# twister3-controller.net
KiCad netlist of a schematic drawn in EAGLE
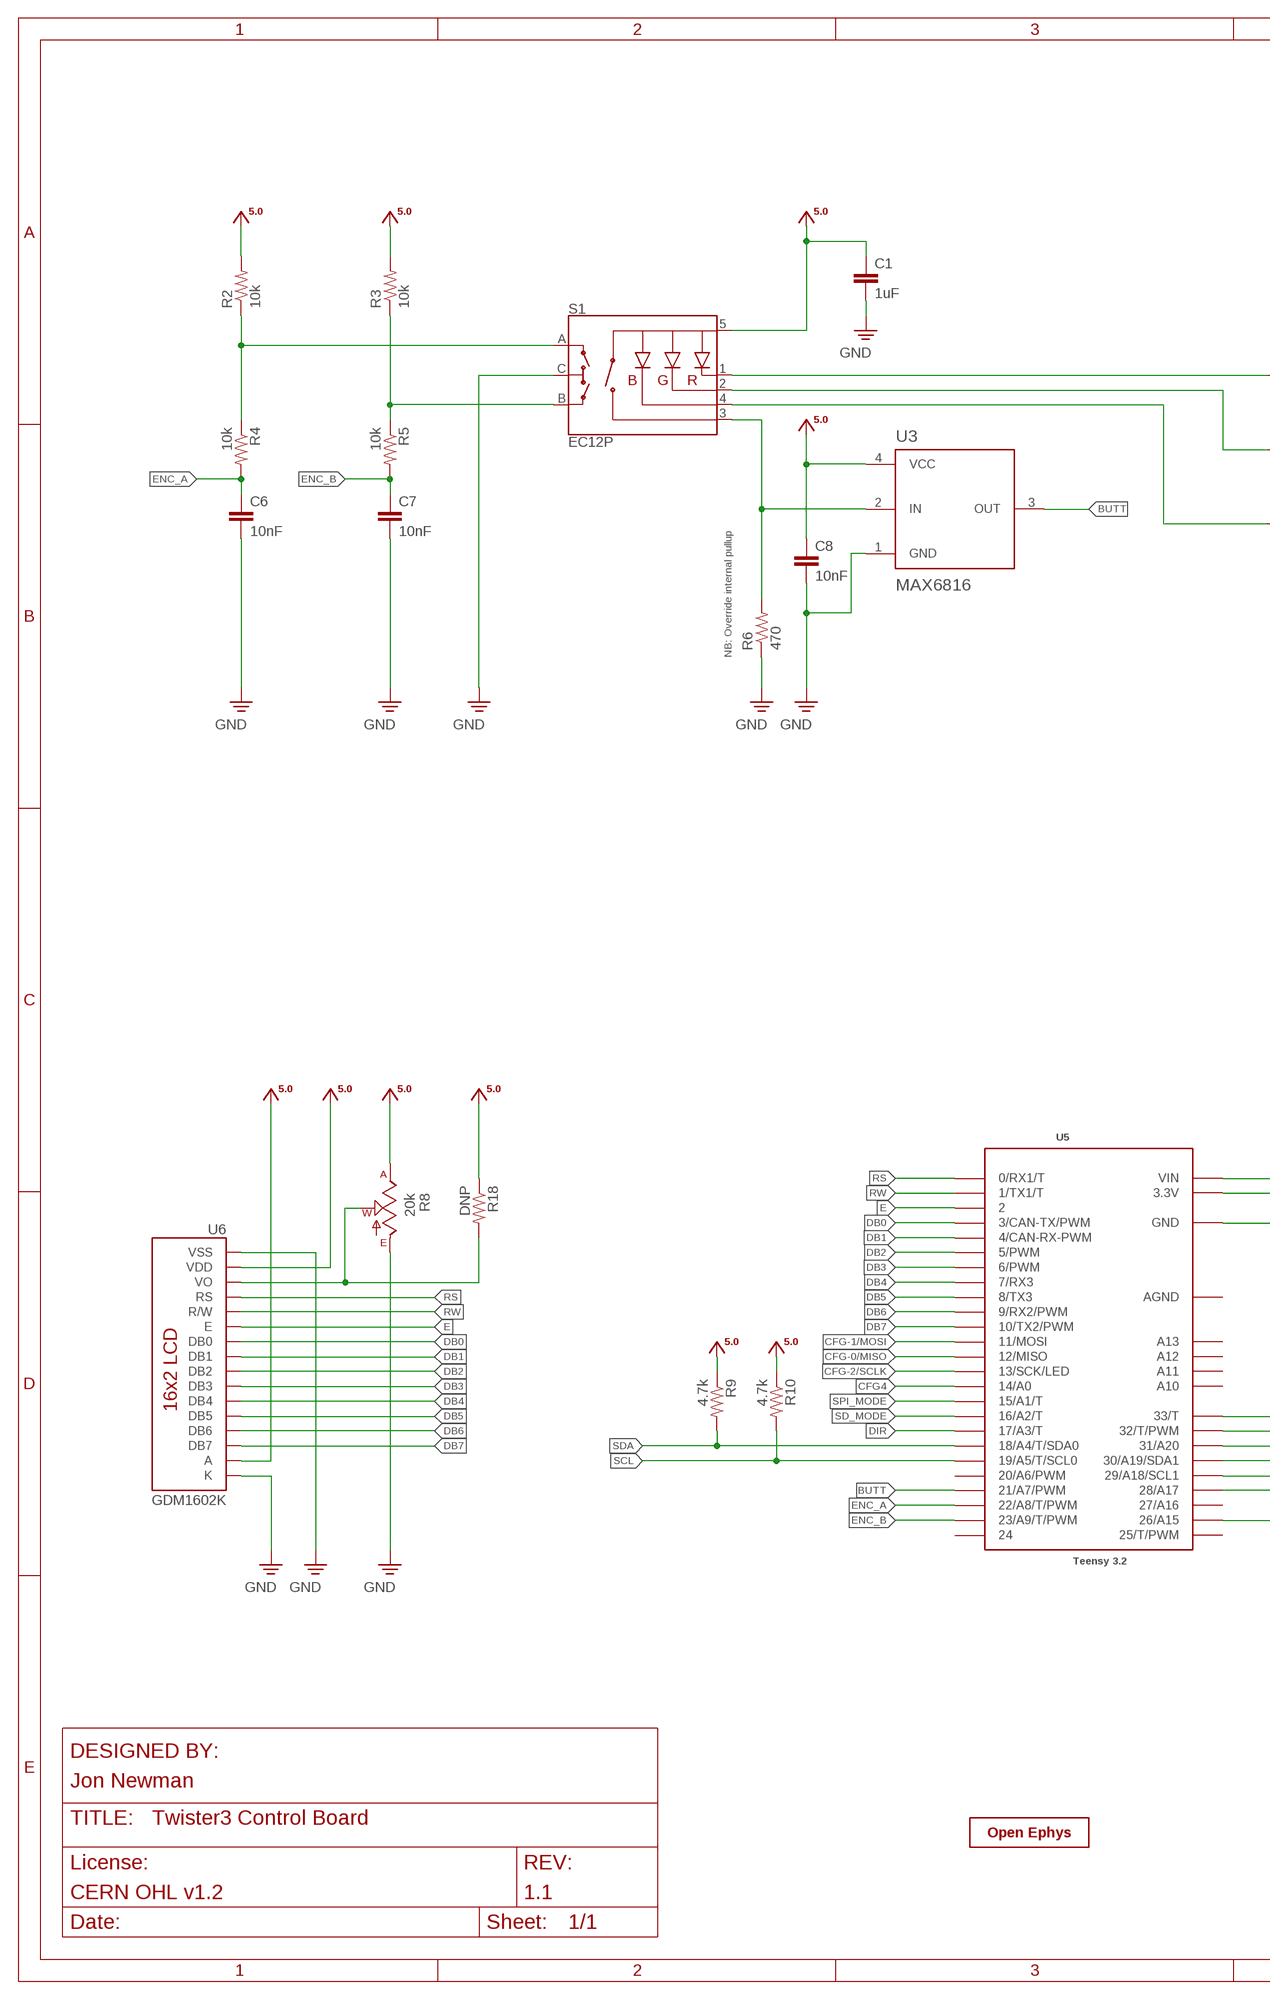
[diagram p0: schematic, sheet 1, part 1 of 2]
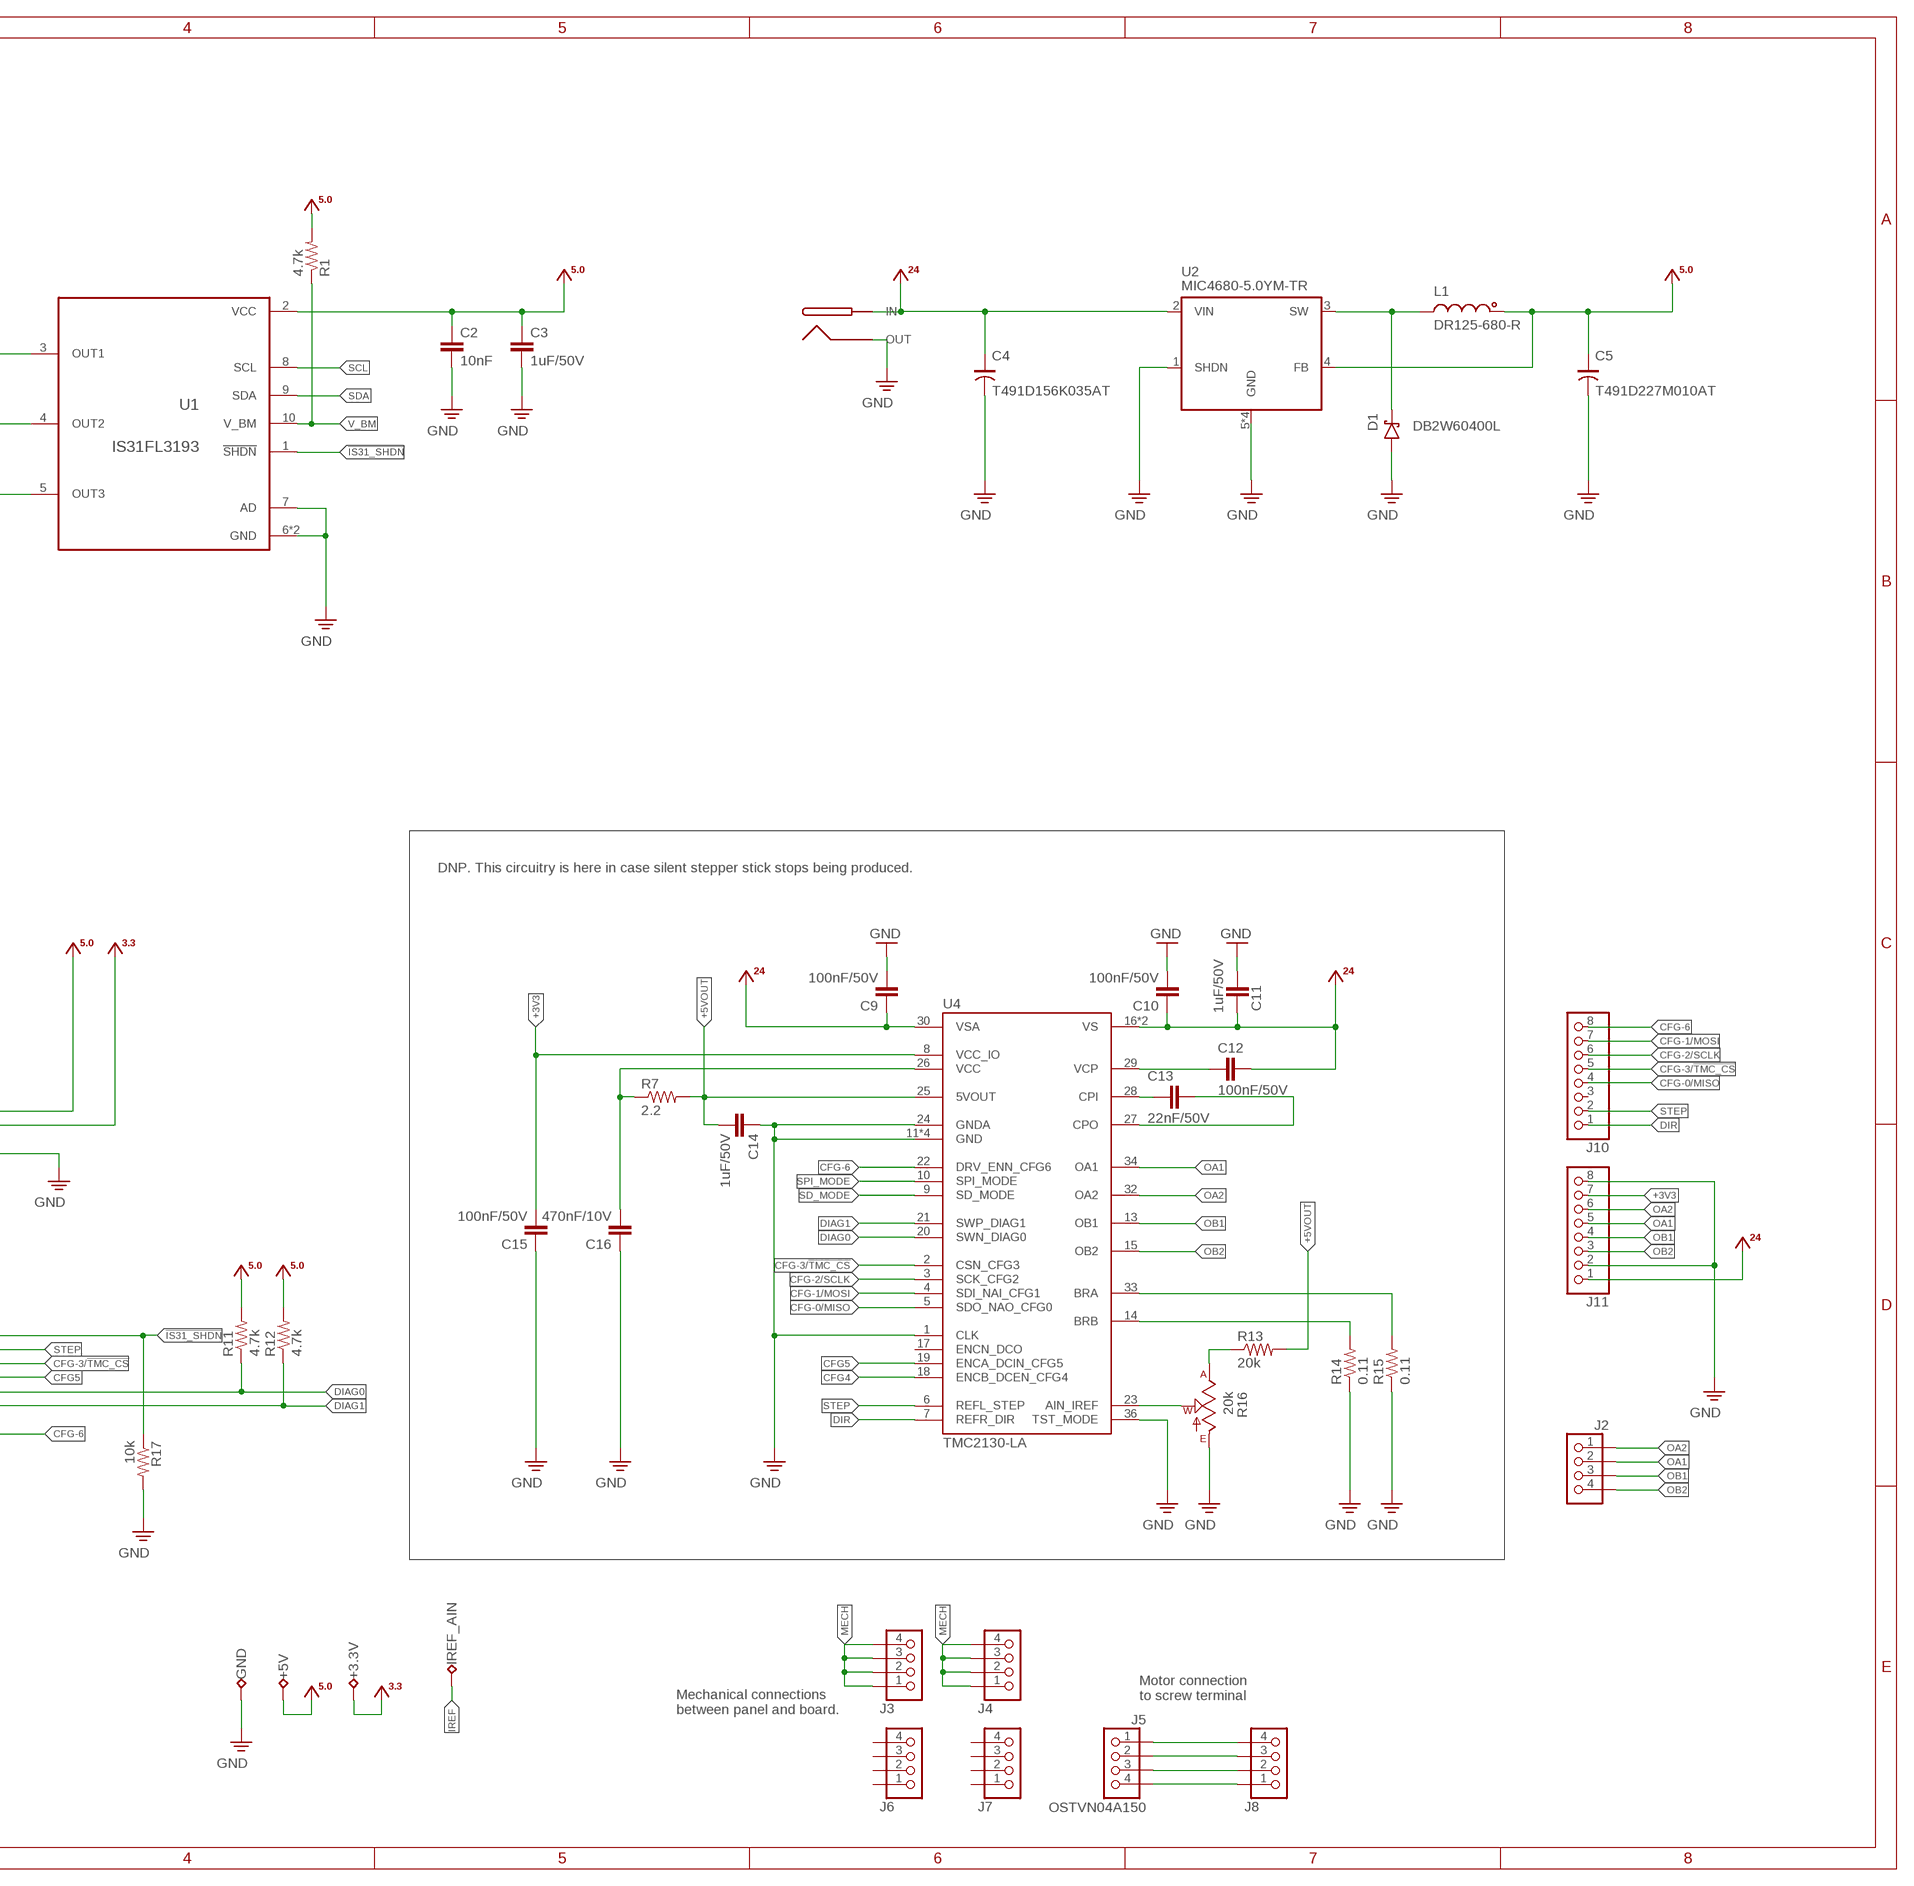
[diagram p1: schematic, sheet 1, part 2 of 2]

(export (version "E")
  (design (tool "Eeschema 10.0.6"))
  (components
    (comp (ref "+3.3V")
      (value "TP_2MM")
      (footprint "eagle-import:TESTPOINT_2MM")
      (libsource (lib "eagle-import") (part "TP_2MM"))
    )
    (comp (ref "+5V")
      (value "TP_2MM")
      (footprint "eagle-import:TESTPOINT_2MM")
      (libsource (lib "eagle-import") (part "TP_2MM"))
    )
    (comp (ref "C1")
      (value "1uF")
      (footprint "eagle-import:0603")
      (libsource (lib "eagle-import") (part "C_0603"))
    )
    (comp (ref "C2")
      (value "10nF")
      (footprint "eagle-import:0603")
      (libsource (lib "eagle-import") (part "C_0603"))
    )
    (comp (ref "C3")
      (value "1uF/50V")
      (footprint "eagle-import:0603")
      (libsource (lib "eagle-import") (part "C_0603"))
    )
    (comp (ref "C4")
      (value "T491D156K035AT")
      (footprint "eagle-import:7343M")
      (libsource (lib "eagle-import") (part "C-POL_7343M"))
    )
    (comp (ref "C5")
      (value "T491D227M010AT")
      (footprint "eagle-import:7343M")
      (libsource (lib "eagle-import") (part "C-POL_7343M"))
    )
    (comp (ref "C6")
      (value "10nF")
      (footprint "eagle-import:0603")
      (libsource (lib "eagle-import") (part "C_0603"))
    )
    (comp (ref "C7")
      (value "10nF")
      (footprint "eagle-import:0603")
      (libsource (lib "eagle-import") (part "C_0603"))
    )
    (comp (ref "C8")
      (value "10nF")
      (footprint "eagle-import:0603")
      (libsource (lib "eagle-import") (part "C_0603"))
    )
    (comp (ref "C9")
      (value "100nF/50V")
      (footprint "eagle-import:0603")
      (libsource (lib "eagle-import") (part "C_0603"))
    )
    (comp (ref "C10")
      (value "100nF/50V")
      (footprint "eagle-import:0603")
      (libsource (lib "eagle-import") (part "C_0603"))
    )
    (comp (ref "C11")
      (value "1uF/50V")
      (footprint "eagle-import:0603")
      (libsource (lib "eagle-import") (part "C_0603"))
    )
    (comp (ref "C12")
      (value "100nF/50V")
      (footprint "eagle-import:0603")
      (libsource (lib "eagle-import") (part "C_0603"))
    )
    (comp (ref "C13")
      (value "22nF/50V")
      (footprint "eagle-import:0402")
      (libsource (lib "eagle-import") (part "C_0402"))
    )
    (comp (ref "C14")
      (value "1uF/50V")
      (footprint "eagle-import:0603")
      (libsource (lib "eagle-import") (part "C_0603"))
    )
    (comp (ref "C15")
      (value "100nF/50V")
      (footprint "eagle-import:0603")
      (libsource (lib "eagle-import") (part "C_0603"))
    )
    (comp (ref "C16")
      (value "470nF/10V")
      (footprint "eagle-import:0402")
      (libsource (lib "eagle-import") (part "C_0402"))
    )
    (comp (ref "D1")
      (value "DB2W60400L")
      (footprint "eagle-import:SOD123")
      (libsource (lib "eagle-import") (part "S-DIODESOD-123"))
    )
    (comp (ref "GND")
      (value "TP_2MM")
      (footprint "eagle-import:TESTPOINT_2MM")
      (libsource (lib "eagle-import") (part "TP_2MM"))
    )
    (comp (ref "IREF_AIN")
      (value "TP_2MM")
      (footprint "eagle-import:TESTPOINT_2MM")
      (libsource (lib "eagle-import") (part "TP_2MM"))
    )
    (comp (ref "J1")
      (value "BARREL-JACK_PJ-063BH")
      (footprint "eagle-import:PJ-063BH")
      (libsource (lib "eagle-import") (part "BARREL-JACK_PJ-063BH"))
    )
    (comp (ref "J2")
      (value "PINHD-1X4")
      (footprint "eagle-import:1X04")
      (libsource (lib "eagle-import") (part "PINHD-1X4"))
    )
    (comp (ref "J3")
      (value "PINHD-1X4_SMD-0.1\"")
      (footprint "eagle-import:JP4_SMD")
      (libsource (lib "eagle-import") (part "PINHD-1X4_SMD-0.1{dblquote}"))
    )
    (comp (ref "J4")
      (value "PINHD-1X4_SMD-0.1\"")
      (footprint "eagle-import:JP4_SMD")
      (libsource (lib "eagle-import") (part "PINHD-1X4_SMD-0.1{dblquote}"))
    )
    (comp (ref "J5")
      (value "OSTVN04A150")
      (footprint "eagle-import:1X04")
      (libsource (lib "eagle-import") (part "PINHD-1X4"))
    )
    (comp (ref "J6")
      (value "PINHD-1X4")
      (footprint "eagle-import:1X04")
      (libsource (lib "eagle-import") (part "PINHD-1X4"))
    )
    (comp (ref "J7")
      (value "PINHD-1X4")
      (footprint "eagle-import:1X04")
      (libsource (lib "eagle-import") (part "PINHD-1X4"))
    )
    (comp (ref "J8")
      (value "PINHD-1X4_SMD-0.1\"")
      (footprint "eagle-import:JP4_SMD")
      (libsource (lib "eagle-import") (part "PINHD-1X4_SMD-0.1{dblquote}"))
    )
    (comp (ref "J10")
      (value "PINHD-1X08_2.54-S")
      (footprint "eagle-import:1X08-S")
      (libsource (lib "eagle-import") (part "PINHD-1X08_2.54-S"))
    )
    (comp (ref "J11")
      (value "PINHD-1X08_2.54-S")
      (footprint "eagle-import:1X08-S")
      (libsource (lib "eagle-import") (part "PINHD-1X08_2.54-S"))
    )
    (comp (ref "L1")
      (value "DR125-680-R")
      (footprint "eagle-import:DR125")
      (libsource (lib "eagle-import") (part "L_DR125"))
    )
    (comp (ref "R1")
      (value "4.7k")
      (footprint "eagle-import:0603")
      (fields (field (name "MPN") "ERJ-3EKFxxxxV"))
      (libsource (lib "eagle-import") (part "jonnew_R_0603"))
    )
    (comp (ref "R2")
      (value "10k")
      (footprint "eagle-import:0603")
      (fields (field (name "MPN") "ERJ-3EKFxxxxV"))
      (libsource (lib "eagle-import") (part "jonnew_R_0603"))
    )
    (comp (ref "R3")
      (value "10k")
      (footprint "eagle-import:0603")
      (fields (field (name "MPN") "ERJ-3EKFxxxxV"))
      (libsource (lib "eagle-import") (part "jonnew_R_0603"))
    )
    (comp (ref "R4")
      (value "10k")
      (footprint "eagle-import:0603")
      (fields (field (name "MPN") "ERJ-3EKFxxxxV"))
      (libsource (lib "eagle-import") (part "jonnew_R_0603"))
    )
    (comp (ref "R5")
      (value "10k")
      (footprint "eagle-import:0603")
      (fields (field (name "MPN") "ERJ-3EKFxxxxV"))
      (libsource (lib "eagle-import") (part "jonnew_R_0603"))
    )
    (comp (ref "R6")
      (value "470")
      (footprint "eagle-import:0603")
      (fields (field (name "MPN") "ERJ-3EKFxxxxV"))
      (libsource (lib "eagle-import") (part "R_0603"))
    )
    (comp (ref "R7")
      (value "2.2")
      (footprint "eagle-import:0402")
      (libsource (lib "eagle-import") (part "jonnew_R_0402"))
    )
    (comp (ref "R8")
      (value "20k")
      (footprint "eagle-import:SM-42_43X")
      (libsource (lib "eagle-import") (part "TRIM_US-SM-42/43X"))
    )
    (comp (ref "R9")
      (value "4.7k")
      (footprint "eagle-import:0603")
      (fields (field (name "MPN") "ERJ-3EKFxxxxV"))
      (libsource (lib "eagle-import") (part "jonnew_R_0603"))
    )
    (comp (ref "R10")
      (value "4.7k")
      (footprint "eagle-import:0603")
      (fields (field (name "MPN") "ERJ-3EKFxxxxV"))
      (libsource (lib "eagle-import") (part "jonnew_R_0603"))
    )
    (comp (ref "R11")
      (value "4.7k")
      (footprint "eagle-import:0603")
      (fields (field (name "MPN") "ERJ-3EKFxxxxV"))
      (libsource (lib "eagle-import") (part "R_0603"))
    )
    (comp (ref "R12")
      (value "4.7k")
      (footprint "eagle-import:0603")
      (fields (field (name "MPN") "ERJ-3EKFxxxxV"))
      (libsource (lib "eagle-import") (part "R_0603"))
    )
    (comp (ref "R13")
      (value "20k")
      (footprint "eagle-import:0603")
      (fields (field (name "MPN") "ERJ-3EKFxxxxV"))
      (libsource (lib "eagle-import") (part "jonnew_R_0603"))
    )
    (comp (ref "R14")
      (value "0.11")
      (footprint "eagle-import:0805")
      (libsource (lib "eagle-import") (part "jonnew_R_0805"))
    )
    (comp (ref "R15")
      (value "0.11")
      (footprint "eagle-import:0805")
      (libsource (lib "eagle-import") (part "jonnew_R_0805"))
    )
    (comp (ref "R16")
      (value "20k")
      (footprint "eagle-import:SM-42_43X")
      (libsource (lib "eagle-import") (part "TRIM_US-SM-42/43X"))
    )
    (comp (ref "R17")
      (value "10k")
      (footprint "eagle-import:0603")
      (fields (field (name "MPN") "ERJ-3EKFxxxxV"))
      (libsource (lib "eagle-import") (part "jonnew_R_0603"))
    )
    (comp (ref "R18")
      (value "DNP")
      (footprint "eagle-import:0603")
      (fields (field (name "MPN") "ERJ-3EKFxxxxV"))
      (libsource (lib "eagle-import") (part "jonnew_R_0603"))
    )
    (comp (ref "S1")
      (value "EC12P")
      (footprint "eagle-import:ENCODER_LED_3")
      (libsource (lib "eagle-import") (part "ENCODER-RGB-SWITCH"))
    )
    (comp (ref "U1")
      (value "IS31FL3193")
      (footprint "eagle-import:PWSON-N10-3X3")
      (libsource (lib "eagle-import") (part "IS31FL3193"))
    )
    (comp (ref "U2")
      (value "MIC4680-5.0YM-TR")
      (footprint "eagle-import:SOIC127P500X400-8N")
      (libsource (lib "eagle-import") (part "MIC4680_SOIC"))
    )
    (comp (ref "U3")
      (value "MAX6816")
      (footprint "eagle-import:SOT143-4")
      (libsource (lib "eagle-import") (part "MAX6816"))
    )
    (comp (ref "U4")
      (value "TMC2130-LA")
      (footprint "eagle-import:QFN36-PAD")
      (libsource (lib "eagle-import") (part "TMC21X0-LA"))
    )
    (comp (ref "U5")
      (value "Teensy 3.2")
      (footprint "eagle-import:TEENSY_3.1_CYCLOPS")
      (libsource (lib "eagle-import") (part "TEENSY_3.1_CYCLOPS"))
    )
    (comp (ref "U6")
      (value "GDM1602K")
      (footprint "eagle-import:LCD-16X2")
      (libsource (lib "eagle-import") (part "LCD-16X2SILK"))
    )
    (comp (ref "X1")
      (value "OE-LOGO_14X10")
      (footprint "eagle-import:OE-LOGO-14X10")
      (libsource (lib "eagle-import") (part "OE-LOGO_14X10"))
    )
  )
  (nets
    (net (code "1") (name "+3V3") (class "Default")
      (node (ref "+3.3V") (pin "1") (pinfunction "TP_1") (pintype "bidirectional"))
      (node (ref "C15") (pin "2") (pinfunction "2_2") (pintype "passive"))
      (node (ref "J11") (pin "7") (pinfunction "7_7") (pintype "passive"))
      (node (ref "U4") (pin "8") (pinfunction "VCC_IO_8") (pintype "power_in"))
      (node (ref "U5") (pin "3.3V") (pinfunction "3.3V_3.3V") (pintype "power_in"))
      (node (ref "U5") (pin "3.3V2") (pinfunction "3.3V_3.3V2") (pintype "power_in"))
    )
    (net (code "2") (name "+5V") (class "Default")
      (node (ref "+5V") (pin "1") (pinfunction "TP_1") (pintype "bidirectional"))
      (node (ref "C1") (pin "1") (pinfunction "1_1") (pintype "passive"))
      (node (ref "C2") (pin "1") (pinfunction "1_1") (pintype "passive"))
      (node (ref "C3") (pin "1") (pinfunction "1_1") (pintype "passive"))
      (node (ref "C5") (pin "+") (pinfunction "+_+") (pintype "passive"))
      (node (ref "C8") (pin "1") (pinfunction "1_1") (pintype "passive"))
      (node (ref "L1") (pin "1") (pinfunction "1_1") (pintype "passive"))
      (node (ref "R1") (pin "2") (pinfunction "2_2") (pintype "passive"))
      (node (ref "R10") (pin "1") (pinfunction "1_1") (pintype "passive"))
      (node (ref "R11") (pin "2") (pinfunction "2_2") (pintype "passive"))
      (node (ref "R12") (pin "2") (pinfunction "2_2") (pintype "passive"))
      (node (ref "R18") (pin "1") (pinfunction "1_1") (pintype "passive"))
      (node (ref "R2") (pin "2") (pinfunction "2_2") (pintype "passive"))
      (node (ref "R3") (pin "2") (pinfunction "2_2") (pintype "passive"))
      (node (ref "R8") (pin "1") (pinfunction "A_1") (pintype "passive"))
      (node (ref "R9") (pin "1") (pinfunction "1_1") (pintype "passive"))
      (node (ref "S1") (pin "5") (pinfunction "+_5") (pintype "passive"))
      (node (ref "U1") (pin "2") (pinfunction "VCC_2") (pintype "power_in"))
      (node (ref "U2") (pin "4") (pinfunction "FB_4") (pintype "input"))
      (node (ref "U3") (pin "4") (pinfunction "VCC_4") (pintype "power_in"))
      (node (ref "U5") (pin "VIN") (pinfunction "VIN_VIN") (pintype "power_in"))
      (node (ref "U6") (pin "15") (pinfunction "A_15") (pintype "power_in"))
      (node (ref "U6") (pin "2") (pinfunction "VDD_2") (pintype "power_in"))
    )
    (net (code "3") (name "+5VOUT") (class "Default")
      (node (ref "C14") (pin "2") (pinfunction "2_2") (pintype "passive"))
      (node (ref "R13") (pin "2") (pinfunction "2_2") (pintype "passive"))
      (node (ref "R7") (pin "2") (pinfunction "2_2") (pintype "passive"))
      (node (ref "U4") (pin "25") (pinfunction "5VOUT_25") (pintype "power_in"))
    )
    (net (code "4") (name "+24V") (class "Default")
      (node (ref "C10") (pin "1") (pinfunction "1_1") (pintype "passive"))
      (node (ref "C11") (pin "1") (pinfunction "1_1") (pintype "passive"))
      (node (ref "C12") (pin "1") (pinfunction "1_1") (pintype "passive"))
      (node (ref "C4") (pin "+") (pinfunction "+_+") (pintype "passive"))
      (node (ref "C9") (pin "1") (pinfunction "1_1") (pintype "passive"))
      (node (ref "J1") (pin "1") (pinfunction "IN_1") (pintype "bidirectional"))
      (node (ref "J11") (pin "1") (pinfunction "1_1") (pintype "passive"))
      (node (ref "U2") (pin "2") (pinfunction "VIN_2") (pintype "power_in"))
      (node (ref "U4") (pin "16") (pinfunction "VS_16") (pintype "power_in"))
      (node (ref "U4") (pin "30") (pinfunction "VSA_30") (pintype "power_in"))
      (node (ref "U4") (pin "31") (pinfunction "VS_31") (pintype "power_in"))
    )
    (net (code "5") (name "/AGND") (class "Default")
      (node (ref "U5") (pin "AGND") (pinfunction "AGND_AGND") (pintype "power_in"))
    )
    (net (code "6") (name "/CFG-3{slash}~{TMC_CS}") (class "Default")
      (node (ref "J10") (pin "5") (pinfunction "5_5") (pintype "passive"))
      (node (ref "U4") (pin "2") (pinfunction "CSN_CFG3_2") (pintype "bidirectional"))
      (node (ref "U5") (pin "31") (pinfunction "31/A20_31") (pintype "bidirectional"))
    )
    (net (code "7") (name "/~{IS31_SHDN}") (class "Default")
      (node (ref "R17") (pin "1") (pinfunction "1_1") (pintype "passive"))
      (node (ref "U1") (pin "1") (pinfunction "~{SHDN}_1") (pintype "input"))
      (node (ref "U5") (pin "33") (pinfunction "33/T_33") (pintype "bidirectional"))
    )
    (net (code "8") (name "BUTT") (class "Default")
      (node (ref "U3") (pin "3") (pinfunction "OUT_3") (pintype "output"))
      (node (ref "U5") (pin "21/A7") (pinfunction "21/A7/PWM_21/A7") (pintype "bidirectional"))
    )
    (net (code "9") (name "CFG-0{slash}MISO") (class "Default")
      (node (ref "J10") (pin "4") (pinfunction "4_4") (pintype "passive"))
      (node (ref "U4") (pin "5") (pinfunction "SDO_NAO_CFG0_5") (pintype "bidirectional"))
      (node (ref "U5") (pin "12") (pinfunction "12/MISO_12") (pintype "bidirectional"))
    )
    (net (code "10") (name "CFG-1{slash}MOSI") (class "Default")
      (node (ref "J10") (pin "7") (pinfunction "7_7") (pintype "passive"))
      (node (ref "U4") (pin "4") (pinfunction "SDI_NAI_CFG1_4") (pintype "bidirectional"))
      (node (ref "U5") (pin "11") (pinfunction "11/MOSI_11") (pintype "bidirectional"))
    )
    (net (code "11") (name "CFG-2{slash}SCLK") (class "Default")
      (node (ref "J10") (pin "6") (pinfunction "6_6") (pintype "passive"))
      (node (ref "U4") (pin "3") (pinfunction "SCK_CFG2_3") (pintype "bidirectional"))
      (node (ref "U5") (pin "13") (pinfunction "13/SCK/LED_13") (pintype "bidirectional"))
    )
    (net (code "12") (name "CFG-6") (class "Default")
      (node (ref "J10") (pin "8") (pinfunction "8_8") (pintype "passive"))
      (node (ref "U4") (pin "22") (pinfunction "DRV_ENN_CFG6_22") (pintype "bidirectional"))
      (node (ref "U5") (pin "26") (pinfunction "26/A15_26") (pintype "bidirectional"))
    )
    (net (code "13") (name "CFG4") (class "Default")
      (node (ref "U4") (pin "18") (pinfunction "ENCB_DCEN_CFG4_18") (pintype "bidirectional"))
      (node (ref "U5") (pin "14/A0") (pinfunction "14/A0_14/A0") (pintype "bidirectional"))
    )
    (net (code "14") (name "CFG5") (class "Default")
      (node (ref "U4") (pin "19") (pinfunction "ENCA_DCIN_CFG5_19") (pintype "bidirectional"))
      (node (ref "U5") (pin "30") (pinfunction "30/A19/SDA1_30") (pintype "bidirectional"))
    )
    (net (code "15") (name "DB0") (class "Default")
      (node (ref "U5") (pin "3") (pinfunction "3/CAN-TX/PWM_3") (pintype "bidirectional"))
      (node (ref "U6") (pin "7") (pinfunction "DB0_7") (pintype "bidirectional"))
    )
    (net (code "16") (name "DB1") (class "Default")
      (node (ref "U5") (pin "4") (pinfunction "4/CAN-RX-PWM_4") (pintype "bidirectional"))
      (node (ref "U6") (pin "8") (pinfunction "DB1_8") (pintype "bidirectional"))
    )
    (net (code "17") (name "DB2") (class "Default")
      (node (ref "U5") (pin "5") (pinfunction "5/PWM_5") (pintype "bidirectional"))
      (node (ref "U6") (pin "9") (pinfunction "DB2_9") (pintype "bidirectional"))
    )
    (net (code "18") (name "DB3") (class "Default")
      (node (ref "U5") (pin "6") (pinfunction "6/PWM_6") (pintype "bidirectional"))
      (node (ref "U6") (pin "10") (pinfunction "DB3_10") (pintype "bidirectional"))
    )
    (net (code "19") (name "DB4") (class "Default")
      (node (ref "U5") (pin "7") (pinfunction "7/RX3_7") (pintype "bidirectional"))
      (node (ref "U6") (pin "11") (pinfunction "DB4_11") (pintype "bidirectional"))
    )
    (net (code "20") (name "DB5") (class "Default")
      (node (ref "U5") (pin "8") (pinfunction "8/TX3_8") (pintype "bidirectional"))
      (node (ref "U6") (pin "12") (pinfunction "DB5_12") (pintype "bidirectional"))
    )
    (net (code "21") (name "DB6") (class "Default")
      (node (ref "U5") (pin "9") (pinfunction "9/RX2/PWM_9") (pintype "bidirectional"))
      (node (ref "U6") (pin "13") (pinfunction "DB6_13") (pintype "bidirectional"))
    )
    (net (code "22") (name "DB7") (class "Default")
      (node (ref "U5") (pin "10") (pinfunction "10/TX2/PWM_10") (pintype "bidirectional"))
      (node (ref "U6") (pin "14") (pinfunction "DB7_14") (pintype "bidirectional"))
    )
    (net (code "23") (name "DIAG0") (class "Default")
      (node (ref "R11") (pin "1") (pinfunction "1_1") (pintype "passive"))
      (node (ref "U4") (pin "20") (pinfunction "SWN_DIAG0_20") (pintype "bidirectional"))
      (node (ref "U5") (pin "29") (pinfunction "29/A18/SCL1_29") (pintype "bidirectional"))
    )
    (net (code "24") (name "DIAG1") (class "Default")
      (node (ref "R12") (pin "1") (pinfunction "1_1") (pintype "passive"))
      (node (ref "U4") (pin "21") (pinfunction "SWP_DIAG1_21") (pintype "bidirectional"))
      (node (ref "U5") (pin "28") (pinfunction "28/A17_28") (pintype "bidirectional"))
    )
    (net (code "25") (name "DIR") (class "Default")
      (node (ref "J10") (pin "1") (pinfunction "1_1") (pintype "passive"))
      (node (ref "U4") (pin "7") (pinfunction "REFR_DIR_7") (pintype "bidirectional"))
      (node (ref "U5") (pin "17/A3") (pinfunction "17/A3/T_17/A3") (pintype "bidirectional"))
    )
    (net (code "26") (name "E") (class "Default")
      (node (ref "U5") (pin "2") (pinfunction "2_2") (pintype "bidirectional"))
      (node (ref "U6") (pin "6") (pinfunction "E_6") (pintype "input"))
    )
    (net (code "27") (name "ENC_A") (class "Default")
      (node (ref "C6") (pin "1") (pinfunction "1_1") (pintype "passive"))
      (node (ref "R4") (pin "2") (pinfunction "2_2") (pintype "passive"))
      (node (ref "U5") (pin "22/A8") (pinfunction "22/A8/T/PWM_22/A8") (pintype "bidirectional"))
    )
    (net (code "28") (name "ENC_B") (class "Default")
      (node (ref "C7") (pin "1") (pinfunction "1_1") (pintype "passive"))
      (node (ref "R5") (pin "2") (pinfunction "2_2") (pintype "passive"))
      (node (ref "U5") (pin "23/A9") (pinfunction "23/A9/T/PWM_23/A9") (pintype "bidirectional"))
    )
    (net (code "29") (name "GND") (class "Default")
      (node (ref "C1") (pin "2") (pinfunction "2_2") (pintype "passive"))
      (node (ref "C10") (pin "2") (pinfunction "2_2") (pintype "passive"))
      (node (ref "C11") (pin "2") (pinfunction "2_2") (pintype "passive"))
      (node (ref "C14") (pin "1") (pinfunction "1_1") (pintype "passive"))
      (node (ref "C15") (pin "1") (pinfunction "1_1") (pintype "passive"))
      (node (ref "C16") (pin "1") (pinfunction "1_1") (pintype "passive"))
      (node (ref "C2") (pin "2") (pinfunction "2_2") (pintype "passive"))
      (node (ref "C3") (pin "2") (pinfunction "2_2") (pintype "passive"))
      (node (ref "C4") (pin "-") (pinfunction "-_-") (pintype "passive"))
      (node (ref "C5") (pin "-") (pinfunction "-_-") (pintype "passive"))
      (node (ref "C6") (pin "2") (pinfunction "2_2") (pintype "passive"))
      (node (ref "C7") (pin "2") (pinfunction "2_2") (pintype "passive"))
      (node (ref "C8") (pin "2") (pinfunction "2_2") (pintype "passive"))
      (node (ref "C9") (pin "2") (pinfunction "2_2") (pintype "passive"))
      (node (ref "D1") (pin "A") (pinfunction "A_A") (pintype "passive"))
      (node (ref "GND") (pin "1") (pinfunction "TP_1") (pintype "bidirectional"))
      (node (ref "J1") (pin "2") (pinfunction "OUT_2") (pintype "bidirectional"))
      (node (ref "J11") (pin "2") (pinfunction "2_2") (pintype "passive"))
      (node (ref "J11") (pin "8") (pinfunction "8_8") (pintype "passive"))
      (node (ref "R14") (pin "1") (pinfunction "1_1") (pintype "passive"))
      (node (ref "R15") (pin "1") (pinfunction "1_1") (pintype "passive"))
      (node (ref "R16") (pin "3") (pinfunction "E_3") (pintype "passive"))
      (node (ref "R17") (pin "2") (pinfunction "2_2") (pintype "passive"))
      (node (ref "R6") (pin "1") (pinfunction "1_1") (pintype "passive"))
      (node (ref "R8") (pin "3") (pinfunction "E_3") (pintype "passive"))
      (node (ref "S1") (pin "C") (pinfunction "C_C") (pintype "bidirectional"))
      (node (ref "U1") (pin "6") (pinfunction "GND_6") (pintype "power_in"))
      (node (ref "U1") (pin "7") (pinfunction "AD_7") (pintype "input"))
      (node (ref "U1") (pin "PAD") (pinfunction "GND_PAD") (pintype "power_in"))
      (node (ref "U2") (pin "1") (pinfunction "SHDN_1") (pintype "input"))
      (node (ref "U2") (pin "5") (pinfunction "GND_5") (pintype "power_in"))
      (node (ref "U2") (pin "6") (pinfunction "GND_6") (pintype "power_in"))
      (node (ref "U2") (pin "7") (pinfunction "GND_7") (pintype "power_in"))
      (node (ref "U2") (pin "8") (pinfunction "GND_8") (pintype "power_in"))
      (node (ref "U3") (pin "1") (pinfunction "GND_1") (pintype "power_in"))
      (node (ref "U4") (pin "1") (pinfunction "CLK_1") (pintype "bidirectional"))
      (node (ref "U4") (pin "11") (pinfunction "GND_11") (pintype "power_in"))
      (node (ref "U4") (pin "12") (pinfunction "GND_12") (pintype "power_in"))
      (node (ref "U4") (pin "24") (pinfunction "GNDA_24") (pintype "power_in"))
      (node (ref "U4") (pin "35") (pinfunction "GND_35") (pintype "power_in"))
      (node (ref "U4") (pin "36") (pinfunction "TST_MODE_36") (pintype "bidirectional"))
      (node (ref "U4") (pin "TP") (pinfunction "GND_TP") (pintype "power_in"))
      (node (ref "U5") (pin "GND") (pinfunction "GND_GND") (pintype "power_in"))
      (node (ref "U5") (pin "GND2") (pinfunction "GND_GND2") (pintype "power_in"))
      (node (ref "U6") (pin "1") (pinfunction "VSS_1") (pintype "power_in"))
      (node (ref "U6") (pin "16") (pinfunction "K_16") (pintype "power_in"))
    )
    (net (code "30") (name "IREF") (class "Default")
      (node (ref "IREF_AIN") (pin "1") (pinfunction "TP_1") (pintype "bidirectional"))
      (node (ref "R16") (pin "2") (pinfunction "W_2") (pintype "passive"))
      (node (ref "U4") (pin "23") (pinfunction "AIN_IREF_23") (pintype "passive"))
    )
    (net (code "31") (name "MECH") (class "Default")
      (node (ref "J3") (pin "1") (pinfunction "1_1") (pintype "passive"))
      (node (ref "J3") (pin "2") (pinfunction "2_2") (pintype "passive"))
      (node (ref "J3") (pin "3") (pinfunction "3_3") (pintype "passive"))
      (node (ref "J3") (pin "4") (pinfunction "4_4") (pintype "passive"))
      (node (ref "J4") (pin "1") (pinfunction "1_1") (pintype "passive"))
      (node (ref "J4") (pin "2") (pinfunction "2_2") (pintype "passive"))
      (node (ref "J4") (pin "3") (pinfunction "3_3") (pintype "passive"))
      (node (ref "J4") (pin "4") (pinfunction "4_4") (pintype "passive"))
    )
    (net (code "32") (name "Net-(J5-Pad1)") (class "Default")
      (node (ref "J5") (pin "1") (pinfunction "1_1") (pintype "passive"))
      (node (ref "J8") (pin "4") (pinfunction "4_4") (pintype "passive"))
    )
    (net (code "33") (name "Net-(J5-Pad2)") (class "Default")
      (node (ref "J5") (pin "2") (pinfunction "2_2") (pintype "passive"))
      (node (ref "J8") (pin "3") (pinfunction "3_3") (pintype "passive"))
    )
    (net (code "34") (name "Net-(J5-Pad3)") (class "Default")
      (node (ref "J5") (pin "3") (pinfunction "3_3") (pintype "passive"))
      (node (ref "J8") (pin "2") (pinfunction "2_2") (pintype "passive"))
    )
    (net (code "35") (name "Net-(J5-Pad4)") (class "Default")
      (node (ref "J5") (pin "4") (pinfunction "4_4") (pintype "passive"))
      (node (ref "J8") (pin "1") (pinfunction "1_1") (pintype "passive"))
    )
    (net (code "36") (name "Net-(R2-Pad1)") (class "Default")
      (node (ref "R2") (pin "1") (pinfunction "1_1") (pintype "passive"))
      (node (ref "R4") (pin "1") (pinfunction "1_1") (pintype "passive"))
      (node (ref "S1") (pin "A") (pinfunction "A_A") (pintype "bidirectional"))
    )
    (net (code "37") (name "Net-(R3-Pad1)") (class "Default")
      (node (ref "R3") (pin "1") (pinfunction "1_1") (pintype "passive"))
      (node (ref "R5") (pin "1") (pinfunction "1_1") (pintype "passive"))
      (node (ref "S1") (pin "B") (pinfunction "B_B") (pintype "bidirectional"))
    )
    (net (code "38") (name "Net-(R8-W)") (class "Default")
      (node (ref "R18") (pin "2") (pinfunction "2_2") (pintype "passive"))
      (node (ref "R8") (pin "2") (pinfunction "W_2") (pintype "passive"))
      (node (ref "U6") (pin "3") (pinfunction "VO_3") (pintype "bidirectional"))
    )
    (net (code "39") (name "Net-(R16-A)") (class "Default")
      (node (ref "R13") (pin "1") (pinfunction "1_1") (pintype "passive"))
      (node (ref "R16") (pin "1") (pinfunction "A_1") (pintype "passive"))
    )
    (net (code "40") (name "Net-(S1--B)") (class "Default")
      (node (ref "S1") (pin "4") (pinfunction "-B_4") (pintype "passive"))
      (node (ref "U1") (pin "5") (pinfunction "OUT3_5") (pintype "open_collector"))
    )
    (net (code "41") (name "Net-(S1--G)") (class "Default")
      (node (ref "S1") (pin "2") (pinfunction "-G_2") (pintype "passive"))
      (node (ref "U1") (pin "4") (pinfunction "OUT2_4") (pintype "open_collector"))
    )
    (net (code "42") (name "Net-(S1--R)") (class "Default")
      (node (ref "S1") (pin "1") (pinfunction "-R_1") (pintype "passive"))
      (node (ref "U1") (pin "3") (pinfunction "OUT1_3") (pintype "open_collector"))
    )
    (net (code "43") (name "Net-(S1-SW)") (class "Default")
      (node (ref "R6") (pin "2") (pinfunction "2_2") (pintype "passive"))
      (node (ref "S1") (pin "3") (pinfunction "SW_3") (pintype "passive"))
      (node (ref "U3") (pin "2") (pinfunction "IN_2") (pintype "input"))
    )
    (net (code "44") (name "Net-(U2-SW)") (class "Default")
      (node (ref "D1") (pin "C") (pinfunction "C_C") (pintype "passive"))
      (node (ref "L1") (pin "2") (pinfunction "2_2") (pintype "passive"))
      (node (ref "U2") (pin "3") (pinfunction "SW_3") (pintype "bidirectional"))
    )
    (net (code "45") (name "Net-(U4-BRA)") (class "Default")
      (node (ref "R15") (pin "2") (pinfunction "2_2") (pintype "passive"))
      (node (ref "U4") (pin "33") (pinfunction "BRA_33") (pintype "output"))
    )
    (net (code "46") (name "Net-(U4-BRB)") (class "Default")
      (node (ref "R14") (pin "2") (pinfunction "2_2") (pintype "passive"))
      (node (ref "U4") (pin "14") (pinfunction "BRB_14") (pintype "output"))
    )
    (net (code "47") (name "Net-(U4-CPI)") (class "Default")
      (node (ref "C13") (pin "2") (pinfunction "2_2") (pintype "passive"))
      (node (ref "U4") (pin "28") (pinfunction "CPI_28") (pintype "passive"))
    )
    (net (code "48") (name "Net-(U4-CPO)") (class "Default")
      (node (ref "C13") (pin "1") (pinfunction "1_1") (pintype "passive"))
      (node (ref "U4") (pin "27") (pinfunction "CPO_27") (pintype "passive"))
    )
    (net (code "49") (name "Net-(U4-VCC)") (class "Default")
      (node (ref "C16") (pin "2") (pinfunction "2_2") (pintype "passive"))
      (node (ref "R7") (pin "1") (pinfunction "1_1") (pintype "passive"))
      (node (ref "U4") (pin "26") (pinfunction "VCC_26") (pintype "power_in"))
    )
    (net (code "50") (name "Net-(U4-VCP)") (class "Default")
      (node (ref "C12") (pin "2") (pinfunction "2_2") (pintype "passive"))
      (node (ref "U4") (pin "29") (pinfunction "VCP_29") (pintype "passive"))
    )
    (net (code "51") (name "OA1") (class "Default")
      (node (ref "J11") (pin "5") (pinfunction "5_5") (pintype "passive"))
      (node (ref "J2") (pin "2") (pinfunction "2_2") (pintype "passive"))
      (node (ref "U4") (pin "34") (pinfunction "OA1_34") (pintype "output"))
    )
    (net (code "52") (name "OA2") (class "Default")
      (node (ref "J11") (pin "6") (pinfunction "6_6") (pintype "passive"))
      (node (ref "J2") (pin "1") (pinfunction "1_1") (pintype "passive"))
      (node (ref "U4") (pin "32") (pinfunction "OA2_32") (pintype "output"))
    )
    (net (code "53") (name "OB1") (class "Default")
      (node (ref "J11") (pin "4") (pinfunction "4_4") (pintype "passive"))
      (node (ref "J2") (pin "3") (pinfunction "3_3") (pintype "passive"))
      (node (ref "U4") (pin "13") (pinfunction "OB1_13") (pintype "output"))
    )
    (net (code "54") (name "OB2") (class "Default")
      (node (ref "J11") (pin "3") (pinfunction "3_3") (pintype "passive"))
      (node (ref "J2") (pin "4") (pinfunction "4_4") (pintype "passive"))
      (node (ref "U4") (pin "15") (pinfunction "OB2_15") (pintype "output"))
    )
    (net (code "55") (name "RS") (class "Default")
      (node (ref "U5") (pin "0") (pinfunction "0/RX1/T_0") (pintype "bidirectional"))
      (node (ref "U6") (pin "4") (pinfunction "RS_4") (pintype "input"))
    )
    (net (code "56") (name "RW") (class "Default")
      (node (ref "U5") (pin "1") (pinfunction "1/TX1/T_1") (pintype "bidirectional"))
      (node (ref "U6") (pin "5") (pinfunction "R/W_5") (pintype "input"))
    )
    (net (code "57") (name "SCL") (class "Default")
      (node (ref "R10") (pin "2") (pinfunction "2_2") (pintype "passive"))
      (node (ref "U1") (pin "8") (pinfunction "SCL_8") (pintype "input"))
      (node (ref "U5") (pin "19/A5") (pinfunction "19/A5/T/SCL0_19/A5") (pintype "bidirectional"))
    )
    (net (code "58") (name "SDA") (class "Default")
      (node (ref "R9") (pin "2") (pinfunction "2_2") (pintype "passive"))
      (node (ref "U1") (pin "9") (pinfunction "SDA_9") (pintype "input"))
      (node (ref "U5") (pin "18/A4") (pinfunction "18/A4/T/SDA0_18/A4") (pintype "bidirectional"))
    )
    (net (code "59") (name "SD_MODE") (class "Default")
      (node (ref "U4") (pin "9") (pinfunction "SD_MODE_9") (pintype "bidirectional"))
      (node (ref "U5") (pin "16/A2") (pinfunction "16/A2/T_16/A2") (pintype "bidirectional"))
    )
    (net (code "60") (name "SPI_MODE") (class "Default")
      (node (ref "U4") (pin "10") (pinfunction "SPI_MODE_10") (pintype "bidirectional"))
      (node (ref "U5") (pin "15/A1") (pinfunction "15/A1/T_15/A1") (pintype "bidirectional"))
    )
    (net (code "61") (name "STEP") (class "Default")
      (node (ref "J10") (pin "2") (pinfunction "2_2") (pintype "passive"))
      (node (ref "U4") (pin "6") (pinfunction "REFL_STEP_6") (pintype "bidirectional"))
      (node (ref "U5") (pin "32") (pinfunction "32/T/PWM_32") (pintype "bidirectional"))
    )
    (net (code "62") (name "V_BM") (class "Default")
      (node (ref "R1") (pin "1") (pinfunction "1_1") (pintype "passive"))
      (node (ref "U1") (pin "10") (pinfunction "V_BM_10") (pintype "input"))
    )
    (net (code "63") (name "unconnected-(J6-Pad1)") (class "Default")
      (node (ref "J6") (pin "1") (pinfunction "1_1") (pintype "passive"))
    )
    (net (code "64") (name "unconnected-(J6-Pad2)") (class "Default")
      (node (ref "J6") (pin "2") (pinfunction "2_2") (pintype "passive"))
    )
    (net (code "65") (name "unconnected-(J6-Pad3)") (class "Default")
      (node (ref "J6") (pin "3") (pinfunction "3_3") (pintype "passive"))
    )
    (net (code "66") (name "unconnected-(J6-Pad4)") (class "Default")
      (node (ref "J6") (pin "4") (pinfunction "4_4") (pintype "passive"))
    )
    (net (code "67") (name "unconnected-(J7-Pad1)") (class "Default")
      (node (ref "J7") (pin "1") (pinfunction "1_1") (pintype "passive"))
    )
    (net (code "68") (name "unconnected-(J7-Pad2)") (class "Default")
      (node (ref "J7") (pin "2") (pinfunction "2_2") (pintype "passive"))
    )
    (net (code "69") (name "unconnected-(J7-Pad3)") (class "Default")
      (node (ref "J7") (pin "3") (pinfunction "3_3") (pintype "passive"))
    )
    (net (code "70") (name "unconnected-(J7-Pad4)") (class "Default")
      (node (ref "J7") (pin "4") (pinfunction "4_4") (pintype "passive"))
    )
    (net (code "71") (name "unconnected-(J10-Pad3)") (class "Default")
      (node (ref "J10") (pin "3") (pinfunction "3_3") (pintype "passive"))
    )
    (net (code "72") (name "unconnected-(U4-ENCN_DCO-Pad17)") (class "Default")
      (node (ref "U4") (pin "17") (pinfunction "ENCN_DCO_17") (pintype "bidirectional"))
    )
    (net (code "73") (name "unconnected-(U5-20{slash}A6{slash}PWM-Pad20{slash}A6)") (class "Default")
      (node (ref "U5") (pin "20/A6") (pinfunction "20/A6/PWM_20/A6") (pintype "bidirectional"))
    )
    (net (code "74") (name "unconnected-(U5-25{slash}T{slash}PWM-Pad25)") (class "Default")
      (node (ref "U5") (pin "25") (pinfunction "25/T/PWM_25") (pintype "bidirectional"))
    )
    (net (code "75") (name "unconnected-(U5-27{slash}A16-Pad27)") (class "Default")
      (node (ref "U5") (pin "27") (pinfunction "27/A16_27") (pintype "bidirectional"))
    )
    (net (code "76") (name "unconnected-(U5-Pad24)") (class "Default")
      (node (ref "U5") (pin "24") (pinfunction "24_24") (pintype "bidirectional"))
    )
    (net (code "77") (name "unconnected-(U5-PadA10)") (class "Default")
      (node (ref "U5") (pin "A10") (pinfunction "A10_A10") (pintype "bidirectional"))
    )
    (net (code "78") (name "unconnected-(U5-PadA11)") (class "Default")
      (node (ref "U5") (pin "A11") (pinfunction "A11_A11") (pintype "bidirectional"))
    )
    (net (code "79") (name "unconnected-(U5-PadA12)") (class "Default")
      (node (ref "U5") (pin "A12") (pinfunction "A12_A12") (pintype "bidirectional"))
    )
    (net (code "80") (name "unconnected-(U5-PadA13)") (class "Default")
      (node (ref "U5") (pin "A13") (pinfunction "A13_A13") (pintype "bidirectional"))
    )
  )
)
